# HFXO.net
KiCad netlist of a schematic drawn in Altium Designer
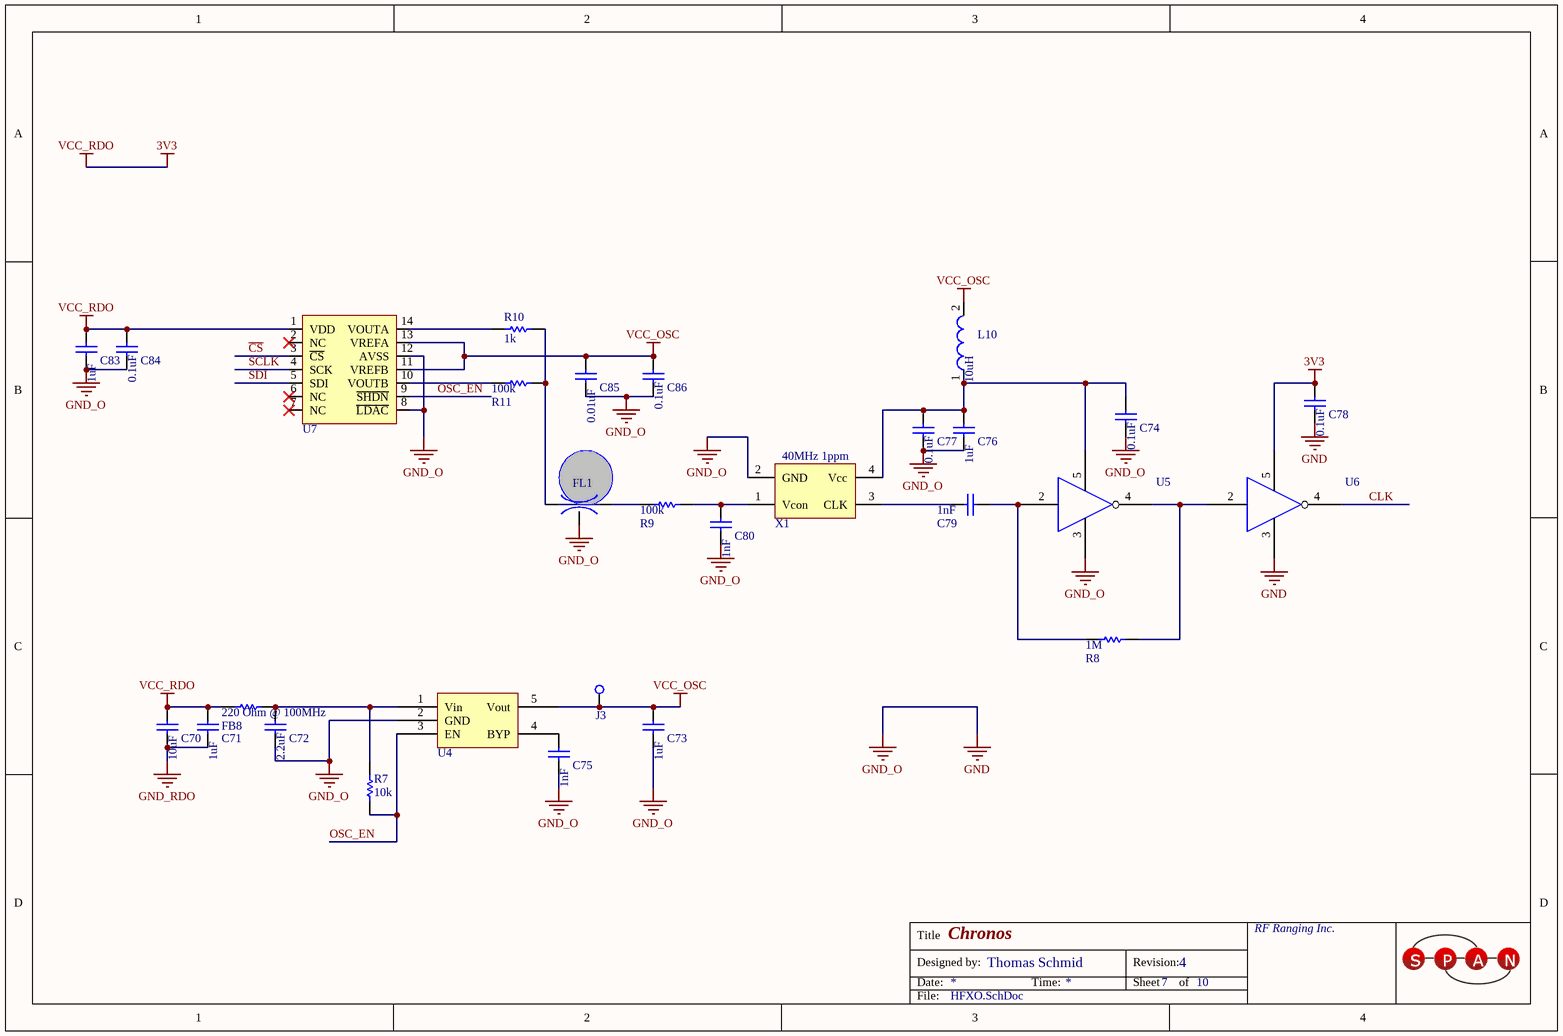
[diagram p0: HFXO.SchDoc]

(export (version "E")
  (design (tool "Eeschema 10.0.6"))
  (components
    (comp (ref "C70")
      (value "GRM188C81C106MA73D")
      (footprint "CAPC1608X08N (0603)")
      (description "CAP CER 10UF 16V 20% X6S 0603")
      (fields
        (field (name "MANUFACTURER") "Murata Electronics North America")
        (field (name "TOLERANCE") "±20%")
      )
      (libsource (lib "Chronos") (part "GRM188C81C106MA73D"))
    )
    (comp (ref "C71")
      (value "GRM188R61A105KA61D")
      (footprint "CAPC1608X08N (0603)")
      (description "CAP CER 1UF 10V 10% X5R 0603")
      (fields
        (field (name "MANUFACTURER") "Murata Electronics North America")
        (field (name "TOLERANCE") "±10%")
      )
      (libsource (lib "Chronos") (part "GRM188R61A105KA61D"))
    )
    (comp (ref "C72")
      (value "GRM188R60J225KE19D")
      (footprint "CAPC1608X08N (0603)")
      (description "CAP CER 2.2UF 6.3V 10% X5R 0603")
      (fields
        (field (name "MANUFACTURER") "Murata Electronics North America")
        (field (name "TOLERANCE") "±10%")
      )
      (libsource (lib "Chronos") (part "GRM188R60J225KE19D"))
    )
    (comp (ref "C73")
      (value "GRM188R61A105KA61D")
      (footprint "CAPC1608X08N (0603)")
      (description "CAP CER 1UF 10V 10% X5R 0603")
      (fields
        (field (name "MANUFACTURER") "Murata Electronics North America")
        (field (name "TOLERANCE") "±10%")
      )
      (libsource (lib "Chronos") (part "GRM188R61A105KA61D"))
    )
    (comp (ref "C74")
      (value "GRM188R71C104KA01D")
      (footprint "CAPC1608X08N (0603)")
      (description "CAP CER 0.1UF 16V 10% X7R 0603")
      (fields
        (field (name "MANUFACTURER") "Murata Electronics North America")
        (field (name "TOLERANCE") "±10%")
      )
      (libsource (lib "Chronos") (part "GRM188R71C104KA01D"))
    )
    (comp (ref "C75")
      (value "GRM1885C1H102JA01D")
      (footprint "CAPC1608X08N (0603)")
      (description "CAP CER 1000PF 50V 5% NP0 0603")
      (fields
        (field (name "MANUFACTURER") "Murata Electronics North America")
        (field (name "TOLERANCE") "±5%")
      )
      (libsource (lib "Chronos") (part "GRM1885C1H102JA01D"))
    )
    (comp (ref "C76")
      (value "GRM188R61A105KA61D")
      (footprint "CAPC1608X08N (0603)")
      (description "CAP CER 1UF 10V 10% X5R 0603")
      (fields
        (field (name "MANUFACTURER") "Murata Electronics North America")
        (field (name "TOLERANCE") "±10%")
      )
      (libsource (lib "Chronos") (part "GRM188R61A105KA61D"))
    )
    (comp (ref "C77")
      (value "GRM188R71C104KA01D")
      (footprint "CAPC1608X08N (0603)")
      (description "CAP CER 0.1UF 16V 10% X7R 0603")
      (fields
        (field (name "MANUFACTURER") "Murata Electronics North America")
        (field (name "TOLERANCE") "±10%")
      )
      (libsource (lib "Chronos") (part "GRM188R71C104KA01D"))
    )
    (comp (ref "C78")
      (value "GRM188R71C104KA01D")
      (footprint "CAPC1608X08N (0603)")
      (description "CAP CER 0.1UF 16V 10% X7R 0603")
      (fields
        (field (name "MANUFACTURER") "Murata Electronics North America")
        (field (name "TOLERANCE") "±10%")
      )
      (libsource (lib "Chronos") (part "GRM188R71C104KA01D"))
    )
    (comp (ref "C79")
      (value "GRM1885C1H102JA01D")
      (footprint "CAPC1608X08N (0603)")
      (description "CAP CER 1000PF 50V 5% NP0 0603")
      (fields
        (field (name "MANUFACTURER") "Murata Electronics North America")
        (field (name "TOLERANCE") "±5%")
      )
      (libsource (lib "Chronos") (part "GRM1885C1H102JA01D"))
    )
    (comp (ref "C80")
      (value "GRM1885C1H102JA01D")
      (footprint "CAPC1608X08N (0603)")
      (description "CAP CER 1000PF 50V 5% NP0 0603")
      (fields
        (field (name "MANUFACTURER") "Murata Electronics North America")
        (field (name "TOLERANCE") "±5%")
      )
      (libsource (lib "Chronos") (part "GRM1885C1H102JA01D"))
    )
    (comp (ref "C83")
      (value "GRM188R61A105KA61D")
      (footprint "CAPC1608X08N (0603)")
      (description "CAP CER 1UF 10V 10% X5R 0603")
      (fields
        (field (name "MANUFACTURER") "Murata Electronics North America")
        (field (name "TOLERANCE") "±10%")
      )
      (libsource (lib "Chronos") (part "GRM188R61A105KA61D"))
    )
    (comp (ref "C84")
      (value "GRM188R71C104KA01D")
      (footprint "CAPC1608X08N (0603)")
      (description "CAP CER 0.1UF 16V 10% X7R 0603")
      (fields
        (field (name "MANUFACTURER") "Murata Electronics North America")
        (field (name "TOLERANCE") "±10%")
      )
      (libsource (lib "Chronos") (part "GRM188R71C104KA01D"))
    )
    (comp (ref "C85")
      (value "GRM188R71C103KA01D")
      (footprint "CAPC1608X08N (0603)")
      (description "CAP CER 10000PF 16V 10% X7R 0603")
      (fields
        (field (name "MANUFACTURER") "Murata Electronics North America")
        (field (name "TOLERANCE") "±10%")
      )
      (libsource (lib "Chronos") (part "GRM188R71C103KA01D"))
    )
    (comp (ref "C86")
      (value "GRM188R71C104KA01D")
      (footprint "CAPC1608X08N (0603)")
      (description "CAP CER 0.1UF 16V 10% X7R 0603")
      (fields
        (field (name "MANUFACTURER") "Murata Electronics North America")
        (field (name "TOLERANCE") "±10%")
      )
      (libsource (lib "Chronos") (part "GRM188R71C104KA01D"))
    )
    (comp (ref "FB8")
      (value "BLM18BD221SN1D")
      (footprint "RESC1608X06N (0603)")
      (description "FERRITE CHIP 220 OHM 200MA 0603")
      (fields (field (name "MANUFACTURER") "Murata Electronics North America"))
      (libsource (lib "Chronos") (part "BLM18BD221SN1D"))
    )
    (comp (ref "FL1")
      (value "NFM21CC223R1H3D")
      (footprint "NFM21C")
      (description "FILTER LC HIGH FREQ 22000PF 0805")
      (fields (field (name "MANUFACTURER") "Murata Electronics North America") (field (name "VOLTAGE") "50V"))
      (libsource (lib "Chronos") (part "NFM21CC223R1H3D"))
    )
    (comp (ref "J3")
      (value "5004")
      (footprint "TP")
      (description "TEST POINT PC MINI .040\"D YELLOW")
      (fields (field (name "MANUFACTURER") "Keystone Electronics"))
      (libsource (lib "Chronos") (part "5004"))
    )
    (comp (ref "L10")
      (value "LQM18FN100M00D")
      (footprint "INDC1608X08N")
      (description "INDUCTOR 10UH 50MA 0603")
      (fields
        (field (name "MANUFACTURER") "Murata Electronics North America")
        (field (name "TOLERANCE") "±20%")
      )
      (libsource (lib "Chronos") (part "LQM18FN100M00D"))
    )
    (comp (ref "R7")
      (value "10k")
      (footprint "RESC1608X06N (0603)")
      (description "RES SMD 10K OHM 1% 1/10W 0603")
      (fields
        (field (name "MANUFACTURER") "Rohm Semiconductor")
        (field (name "MANUFACTURER PART NUMBER") "MCR03ERTF1002")
      )
      (libsource (lib "Chronos") (part "MCR03ERTF1002"))
    )
    (comp (ref "R8")
      (value "RC0603FR-071ML")
      (footprint "RESC1608X06N (0603)")
      (description "RES 1.00M OHM 1/10W 1% 0603 SMD")
      (fields (field (name "MANUFACTURER") "Yageo") (field (name "TOLERANCE") "±1%"))
      (libsource (lib "Chronos") (part "RC0603FR-071ML"))
    )
    (comp (ref "R9")
      (value "RC0603FR-07100KL")
      (footprint "RESC1608X06N (0603)")
      (description "RES 100K OHM 1/10W 1% 0603 SMD")
      (fields (field (name "MANUFACTURER") "Yageo") (field (name "TOLERANCE") "±1%"))
      (libsource (lib "Chronos") (part "RC0603FR-07100KL"))
    )
    (comp (ref "R10")
      (value "1k")
      (description "RES SMD 1K OHM 1% 1/10W 0603")
      (fields
        (field (name "MANUFACTURER") "Vishay Dale")
        (field (name "MANUFACTURER PART NUMBER") "CRCW06031K00FKEA")
      )
      (libsource (lib "Chronos") (part "CRCW06031K00FKEA"))
    )
    (comp (ref "R11")
      (value "RC0603FR-07100KL")
      (footprint "RESC1608X06N (0603)")
      (description "RES 100K OHM 1/10W 1% 0603 SMD")
      (fields (field (name "MANUFACTURER") "Yageo") (field (name "TOLERANCE") "±1%"))
      (libsource (lib "Chronos") (part "RC0603FR-07100KL"))
    )
    (comp (ref "U4")
      (value "FAN2500S30X")
      (footprint "SOT95P280X145-5N")
      (description "IC REG LDO 3V 0.1A SOT23-5")
      (fields (field (name "MANUFACTURER") "Fairchild Semiconductor"))
      (libsource (lib "Chronos") (part "FAN2500S30X"))
    )
    (comp (ref "U5")
      (value "NC7SPU04P5X")
      (footprint "SC70")
      (description "IC INVERTER ULP UNBUFF SC70-5")
      (fields (field (name "MANUFACTURER") "Fairchild Semiconductor"))
      (libsource (lib "Chronos") (part "NC7SPU04P5X"))
    )
    (comp (ref "U6")
      (value "NC7SPU04P5X")
      (footprint "SC70")
      (description "IC INVERTER ULP UNBUFF SC70-5")
      (fields (field (name "MANUFACTURER") "Fairchild Semiconductor"))
      (libsource (lib "Chronos") (part "NC7SPU04P5X"))
    )
    (comp (ref "U7")
      (value "MCP4922-E/ST")
      (footprint "TSOP65P640X110-14N")
      (description "IC DAC 12BIT DUAL W/SPI 14TSSOP")
      (fields (field (name "MANUFACTURER") "Microchip Technology"))
      (libsource (lib "Chronos") (part "MCP4922-E/ST"))
    )
    (comp (ref "X1")
      (value "ASVTX-12-A-40.000MHZ-H10-T")
      (footprint "2.5x2.0x0.9mmXTAL")
      (description "OSC VCTCXO 40.000MHZ SNWV SMD")
      (fields (field (name "MANUFACTURER") "Abracon Corporation"))
      (libsource (lib "Chronos") (part "ASVTX-12-A-40.000MHZ-H10-T"))
    )
  )
  (nets
    (net (code "1") (name "/CLK") (class "Default")
      (node (ref "U6") (pin "4") (pinfunction "4_4") (pintype "passive"))
    )
    (net (code "2") (name "/OSC_EN") (class "Default")
      (node (ref "R7") (pin "1") (pinfunction "1_1") (pintype "passive"))
      (node (ref "U4") (pin "3") (pinfunction "EN_3") (pintype "passive"))
      (node (ref "U7") (pin "9") (pinfunction "~{SHDN}_9") (pintype "passive"))
    )
    (net (code "3") (name "/SCLK") (class "Default")
      (node (ref "U7") (pin "4") (pinfunction "SCK_4") (pintype "passive"))
    )
    (net (code "4") (name "/SDI") (class "Default")
      (node (ref "U7") (pin "5") (pinfunction "SDI_5") (pintype "passive"))
    )
    (net (code "5") (name "/~{CS}") (class "Default")
      (node (ref "U7") (pin "3") (pinfunction "~{CS}_3") (pintype "passive"))
    )
    (net (code "6") (name "3V3") (class "Default")
      (node (ref "C70") (pin "2") (pinfunction "2_2") (pintype "passive"))
      (node (ref "C71") (pin "2") (pinfunction "2_2") (pintype "passive"))
      (node (ref "C78") (pin "2") (pinfunction "2_2") (pintype "passive"))
      (node (ref "C83") (pin "2") (pinfunction "2_2") (pintype "passive"))
      (node (ref "C84") (pin "2") (pinfunction "2_2") (pintype "passive"))
      (node (ref "FB8") (pin "1") (pinfunction "1_1") (pintype "passive"))
      (node (ref "U6") (pin "5") (pinfunction "5_5") (pintype "passive"))
      (node (ref "U7") (pin "1") (pinfunction "VDD_1") (pintype "passive"))
    )
    (net (code "7") (name "GND") (class "Default")
      (node (ref "C72") (pin "1") (pinfunction "1_1") (pintype "passive"))
      (node (ref "C73") (pin "1") (pinfunction "1_1") (pintype "passive"))
      (node (ref "C74") (pin "1") (pinfunction "1_1") (pintype "passive"))
      (node (ref "C75") (pin "1") (pinfunction "1_1") (pintype "passive"))
      (node (ref "C76") (pin "1") (pinfunction "1_1") (pintype "passive"))
      (node (ref "C77") (pin "1") (pinfunction "1_1") (pintype "passive"))
      (node (ref "C78") (pin "1") (pinfunction "1_1") (pintype "passive"))
      (node (ref "C80") (pin "1") (pinfunction "1_1") (pintype "passive"))
      (node (ref "C83") (pin "1") (pinfunction "1_1") (pintype "passive"))
      (node (ref "C84") (pin "1") (pinfunction "1_1") (pintype "passive"))
      (node (ref "C85") (pin "1") (pinfunction "1_1") (pintype "passive"))
      (node (ref "C86") (pin "1") (pinfunction "1_1") (pintype "passive"))
      (node (ref "FL1") (pin "2") (pinfunction "2_2") (pintype "passive"))
      (node (ref "U4") (pin "2") (pinfunction "GND_2") (pintype "passive"))
      (node (ref "U5") (pin "3") (pinfunction "3_3") (pintype "passive"))
      (node (ref "U6") (pin "3") (pinfunction "3_3") (pintype "passive"))
      (node (ref "U7") (pin "12") (pinfunction "AVSS_12") (pintype "passive"))
      (node (ref "U7") (pin "8") (pinfunction "~{LDAC}_8") (pintype "passive"))
      (node (ref "X1") (pin "2") (pinfunction "GND_2") (pintype "passive"))
    )
    (net (code "8") (name "GND_RDO") (class "Default")
      (node (ref "C70") (pin "1") (pinfunction "1_1") (pintype "passive"))
      (node (ref "C71") (pin "1") (pinfunction "1_1") (pintype "passive"))
    )
    (net (code "9") (name "Net-(C79-Pad2)") (class "Default")
      (node (ref "C79") (pin "2") (pinfunction "2_2") (pintype "passive"))
      (node (ref "R8") (pin "1") (pinfunction "1_1") (pintype "passive"))
      (node (ref "U5") (pin "2") (pinfunction "2_2") (pintype "passive"))
    )
    (net (code "10") (name "Net-(FL1-Pad1)") (class "Default")
      (node (ref "FL1") (pin "1") (pinfunction "1_1") (pintype "passive"))
      (node (ref "R10") (pin "2") (pinfunction "2_2") (pintype "passive"))
      (node (ref "R11") (pin "2") (pinfunction "2_2") (pintype "passive"))
    )
    (net (code "11") (name "Net-(FL1-Pad3)") (class "Default")
      (node (ref "FL1") (pin "3") (pinfunction "3_3") (pintype "passive"))
      (node (ref "R9") (pin "1") (pinfunction "1_1") (pintype "passive"))
    )
    (net (code "12") (name "Net-(R8-Pad2)") (class "Default")
      (node (ref "R8") (pin "2") (pinfunction "2_2") (pintype "passive"))
      (node (ref "U5") (pin "4") (pinfunction "4_4") (pintype "passive"))
      (node (ref "U6") (pin "2") (pinfunction "2_2") (pintype "passive"))
    )
    (net (code "13") (name "Net-(U4-BYP)") (class "Default")
      (node (ref "C75") (pin "2") (pinfunction "2_2") (pintype "passive"))
      (node (ref "U4") (pin "4") (pinfunction "BYP_4") (pintype "passive"))
    )
    (net (code "14") (name "Net-(U4-Vin)") (class "Default")
      (node (ref "C72") (pin "2") (pinfunction "2_2") (pintype "passive"))
      (node (ref "FB8") (pin "2") (pinfunction "2_2") (pintype "passive"))
      (node (ref "R7") (pin "2") (pinfunction "2_2") (pintype "passive"))
      (node (ref "U4") (pin "1") (pinfunction "Vin_1") (pintype "passive"))
    )
    (net (code "15") (name "Net-(U7-VOUTA)") (class "Default")
      (node (ref "R10") (pin "1") (pinfunction "1_1") (pintype "passive"))
      (node (ref "U7") (pin "14") (pinfunction "VOUTA_14") (pintype "passive"))
    )
    (net (code "16") (name "Net-(U7-VOUTB)") (class "Default")
      (node (ref "R11") (pin "1") (pinfunction "1_1") (pintype "passive"))
      (node (ref "U7") (pin "10") (pinfunction "VOUTB_10") (pintype "passive"))
    )
    (net (code "17") (name "Net-(X1-CLK)") (class "Default")
      (node (ref "C79") (pin "1") (pinfunction "1_1") (pintype "passive"))
      (node (ref "X1") (pin "3") (pinfunction "CLK_3") (pintype "passive"))
    )
    (net (code "18") (name "Net-(X1-Vcc)") (class "Default")
      (node (ref "C74") (pin "2") (pinfunction "2_2") (pintype "passive"))
      (node (ref "C76") (pin "2") (pinfunction "2_2") (pintype "passive"))
      (node (ref "C77") (pin "2") (pinfunction "2_2") (pintype "passive"))
      (node (ref "L10") (pin "1") (pinfunction "1_1") (pintype "passive"))
      (node (ref "U5") (pin "5") (pinfunction "5_5") (pintype "passive"))
      (node (ref "X1") (pin "4") (pinfunction "Vcc_4") (pintype "passive"))
    )
    (net (code "19") (name "Net-(X1-Vcon)") (class "Default")
      (node (ref "C80") (pin "2") (pinfunction "2_2") (pintype "passive"))
      (node (ref "R9") (pin "2") (pinfunction "2_2") (pintype "passive"))
      (node (ref "X1") (pin "1") (pinfunction "Vcon_1") (pintype "passive"))
    )
    (net (code "20") (name "VCC_OSC") (class "Default")
      (node (ref "C73") (pin "2") (pinfunction "2_2") (pintype "passive"))
      (node (ref "C85") (pin "2") (pinfunction "2_2") (pintype "passive"))
      (node (ref "C86") (pin "2") (pinfunction "2_2") (pintype "passive"))
      (node (ref "J3") (pin "1") (pinfunction "1_1") (pintype "passive"))
      (node (ref "L10") (pin "2") (pinfunction "2_2") (pintype "passive"))
      (node (ref "U4") (pin "5") (pinfunction "Vout_5") (pintype "passive"))
      (node (ref "U7") (pin "11") (pinfunction "VREFB_11") (pintype "passive"))
      (node (ref "U7") (pin "13") (pinfunction "VREFA_13") (pintype "passive"))
    )
    (net (code "21") (name "unconnected-(U5-Pad1)") (class "Default")
      (node (ref "U5") (pin "1") (pinfunction "1_1") (pintype "passive"))
    )
    (net (code "22") (name "unconnected-(U6-Pad1)") (class "Default")
      (node (ref "U6") (pin "1") (pinfunction "1_1") (pintype "passive"))
    )
    (net (code "23") (name "unconnected-(U7-NC-Pad2)") (class "Default")
      (node (ref "U7") (pin "2") (pinfunction "NC_2") (pintype "passive+no_connect"))
    )
    (net (code "24") (name "unconnected-(U7-NC-Pad6)") (class "Default")
      (node (ref "U7") (pin "6") (pinfunction "NC_6") (pintype "passive+no_connect"))
    )
    (net (code "25") (name "unconnected-(U7-NC-Pad7)") (class "Default")
      (node (ref "U7") (pin "7") (pinfunction "NC_7") (pintype "passive+no_connect"))
    )
  )
)
